# mpu6050.net
KiCad netlist of a schematic drawn in Altium Designer
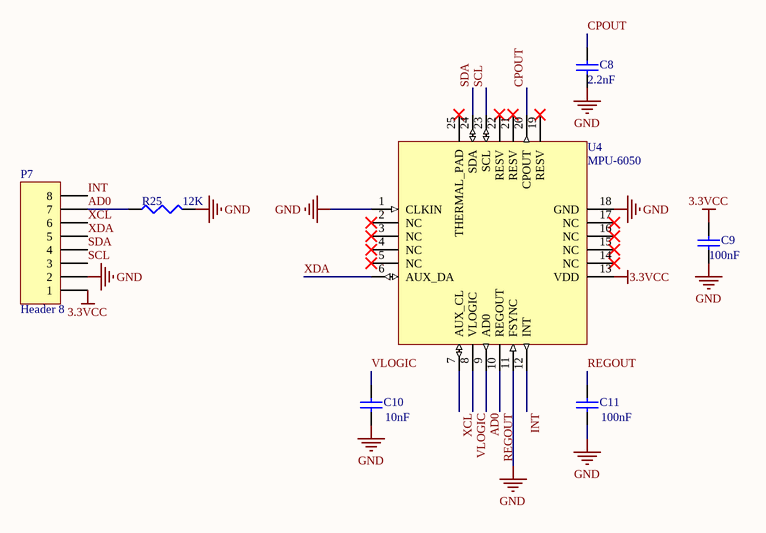
[diagram p0: mpu6050.SchDoc]

(export (version "E")
  (design (tool "Eeschema 10.0.6"))
  (components
    (comp (ref "C8")
      (value "2.2nF")
      (footprint "C1206")
      (description "Capacitor (Semiconductor SIM Model)")
      (fields (field (name "Comment") "Cap Semi") (field (name "PUBLISHER") "Altium Limited"))
      (libsource (lib "Miscellaneous Devices") (part "Cap Semi"))
    )
    (comp (ref "C9")
      (value "100nF")
      (footprint "C1206")
      (description "Capacitor (Semiconductor SIM Model)")
      (fields (field (name "Comment") "Cap Semi") (field (name "PUBLISHER") "Altium Limited"))
      (libsource (lib "Miscellaneous Devices") (part "Cap Semi"))
    )
    (comp (ref "C10")
      (value "10nF")
      (footprint "C1206")
      (description "Capacitor (Semiconductor SIM Model)")
      (fields (field (name "Comment") "Cap Semi") (field (name "PUBLISHER") "Altium Limited"))
      (libsource (lib "Miscellaneous Devices") (part "Cap Semi"))
    )
    (comp (ref "C11")
      (value "100nF")
      (footprint "C1206")
      (description "Capacitor (Semiconductor SIM Model)")
      (fields (field (name "Comment") "Cap Semi") (field (name "PUBLISHER") "Altium Limited"))
      (libsource (lib "Miscellaneous Devices") (part "Cap Semi"))
    )
    (comp (ref "P7")
      (value "Header 8")
      (footprint "HDR1X8")
      (description "Header, 8-Pin")
      (fields (field (name "PUBLISHER") "Altium Limited"))
      (libsource (lib "Miscellaneous Connectors") (part "Header 8"))
    )
    (comp (ref "R25")
      (value "12K")
      (footprint "J1-0603")
      (description "Resistor")
      (fields (field (name "Comment") "Res3") (field (name "PUBLISHER") "Altium Limited"))
      (libsource (lib "Miscellaneous Devices") (part "Res3"))
    )
    (comp (ref "U4")
      (value "MPU-6050")
      (footprint "QFN50P400X400X95-25N")
      (description "INVENSENSE - Módulo MEMS, Giroscopio de Tres Ejes, Acelerómetro de Tres Ejes")
      (libsource (lib "ecubelib") (part "MPU-6050"))
    )
  )
  (nets
    (net (code "1") (name "/AD0") (class "Default")
      (node (ref "P7") (pin "7") (pinfunction "7_7") (pintype "passive"))
      (node (ref "R25") (pin "1") (pinfunction "1_1") (pintype "passive"))
      (node (ref "U4") (pin "9") (pinfunction "AD0_9") (pintype "output"))
    )
    (net (code "2") (name "/CPOUT") (class "Default")
      (node (ref "C8") (pin "2") (pinfunction "2_2") (pintype "passive"))
      (node (ref "U4") (pin "20") (pinfunction "CPOUT_20") (pintype "output"))
    )
    (net (code "3") (name "/INT") (class "Default")
      (node (ref "P7") (pin "8") (pinfunction "8_8") (pintype "passive"))
      (node (ref "U4") (pin "12") (pinfunction "INT_12") (pintype "output"))
    )
    (net (code "4") (name "/REGOUT") (class "Default")
      (node (ref "C11") (pin "2") (pinfunction "2_2") (pintype "passive"))
      (node (ref "U4") (pin "10") (pinfunction "REGOUT_10") (pintype "passive"))
    )
    (net (code "5") (name "/SCL") (class "Default")
      (node (ref "P7") (pin "3") (pinfunction "3_3") (pintype "passive"))
      (node (ref "U4") (pin "23") (pinfunction "SCL_23") (pintype "bidirectional"))
    )
    (net (code "6") (name "/SDA") (class "Default")
      (node (ref "P7") (pin "4") (pinfunction "4_4") (pintype "passive"))
      (node (ref "U4") (pin "24") (pinfunction "SDA_24") (pintype "bidirectional"))
    )
    (net (code "7") (name "/VLOGIC") (class "Default")
      (node (ref "C10") (pin "2") (pinfunction "2_2") (pintype "passive"))
      (node (ref "U4") (pin "8") (pinfunction "VLOGIC_8") (pintype "power_in"))
    )
    (net (code "8") (name "/XCL") (class "Default")
      (node (ref "P7") (pin "6") (pinfunction "6_6") (pintype "passive"))
      (node (ref "U4") (pin "7") (pinfunction "AUX_CL_7") (pintype "bidirectional"))
    )
    (net (code "9") (name "/XDA") (class "Default")
      (node (ref "P7") (pin "5") (pinfunction "5_5") (pintype "passive"))
      (node (ref "U4") (pin "6") (pinfunction "AUX_DA_6") (pintype "bidirectional"))
    )
    (net (code "10") (name "3.3VCC") (class "Default")
      (node (ref "C9") (pin "2") (pinfunction "2_2") (pintype "passive"))
      (node (ref "P7") (pin "1") (pinfunction "1_1") (pintype "passive"))
      (node (ref "U4") (pin "13") (pinfunction "VDD_13") (pintype "power_in"))
    )
    (net (code "11") (name "GND") (class "Default")
      (node (ref "C10") (pin "1") (pinfunction "1_1") (pintype "passive"))
      (node (ref "C11") (pin "1") (pinfunction "1_1") (pintype "passive"))
      (node (ref "C8") (pin "1") (pinfunction "1_1") (pintype "passive"))
      (node (ref "C9") (pin "1") (pinfunction "1_1") (pintype "passive"))
      (node (ref "P7") (pin "2") (pinfunction "2_2") (pintype "passive"))
      (node (ref "R25") (pin "2") (pinfunction "2_2") (pintype "passive"))
      (node (ref "U4") (pin "1") (pinfunction "CLKIN_1") (pintype "input"))
      (node (ref "U4") (pin "11") (pinfunction "FSYNC_11") (pintype "input"))
      (node (ref "U4") (pin "18") (pinfunction "GND_18") (pintype "power_in"))
    )
    (net (code "12") (name "unconnected-(U4-NC-Pad2)") (class "Default")
      (node (ref "U4") (pin "2") (pinfunction "NC_2") (pintype "passive+no_connect"))
    )
    (net (code "13") (name "unconnected-(U4-NC-Pad3)") (class "Default")
      (node (ref "U4") (pin "3") (pinfunction "NC_3") (pintype "passive+no_connect"))
    )
    (net (code "14") (name "unconnected-(U4-NC-Pad4)") (class "Default")
      (node (ref "U4") (pin "4") (pinfunction "NC_4") (pintype "passive+no_connect"))
    )
    (net (code "15") (name "unconnected-(U4-NC-Pad5)") (class "Default")
      (node (ref "U4") (pin "5") (pinfunction "NC_5") (pintype "passive+no_connect"))
    )
    (net (code "16") (name "unconnected-(U4-NC-Pad14)") (class "Default")
      (node (ref "U4") (pin "14") (pinfunction "NC_14") (pintype "passive+no_connect"))
    )
    (net (code "17") (name "unconnected-(U4-NC-Pad15)") (class "Default")
      (node (ref "U4") (pin "15") (pinfunction "NC_15") (pintype "passive+no_connect"))
    )
    (net (code "18") (name "unconnected-(U4-NC-Pad16)") (class "Default")
      (node (ref "U4") (pin "16") (pinfunction "NC_16") (pintype "passive+no_connect"))
    )
    (net (code "19") (name "unconnected-(U4-NC-Pad17)") (class "Default")
      (node (ref "U4") (pin "17") (pinfunction "NC_17") (pintype "passive+no_connect"))
    )
    (net (code "20") (name "unconnected-(U4-RESV-Pad19)") (class "Default")
      (node (ref "U4") (pin "19") (pinfunction "RESV_19") (pintype "passive+no_connect"))
    )
    (net (code "21") (name "unconnected-(U4-RESV-Pad21)") (class "Default")
      (node (ref "U4") (pin "21") (pinfunction "RESV_21") (pintype "passive+no_connect"))
    )
    (net (code "22") (name "unconnected-(U4-RESV-Pad22)") (class "Default")
      (node (ref "U4") (pin "22") (pinfunction "RESV_22") (pintype "passive+no_connect"))
    )
    (net (code "23") (name "unconnected-(U4-THERMAL_PAD-Pad25)") (class "Default")
      (node (ref "U4") (pin "25") (pinfunction "THERMAL_PAD_25") (pintype "passive+no_connect"))
    )
  )
)
